# double_coil_driver.net
KiCad netlist of a schematic drawn in EAGLE
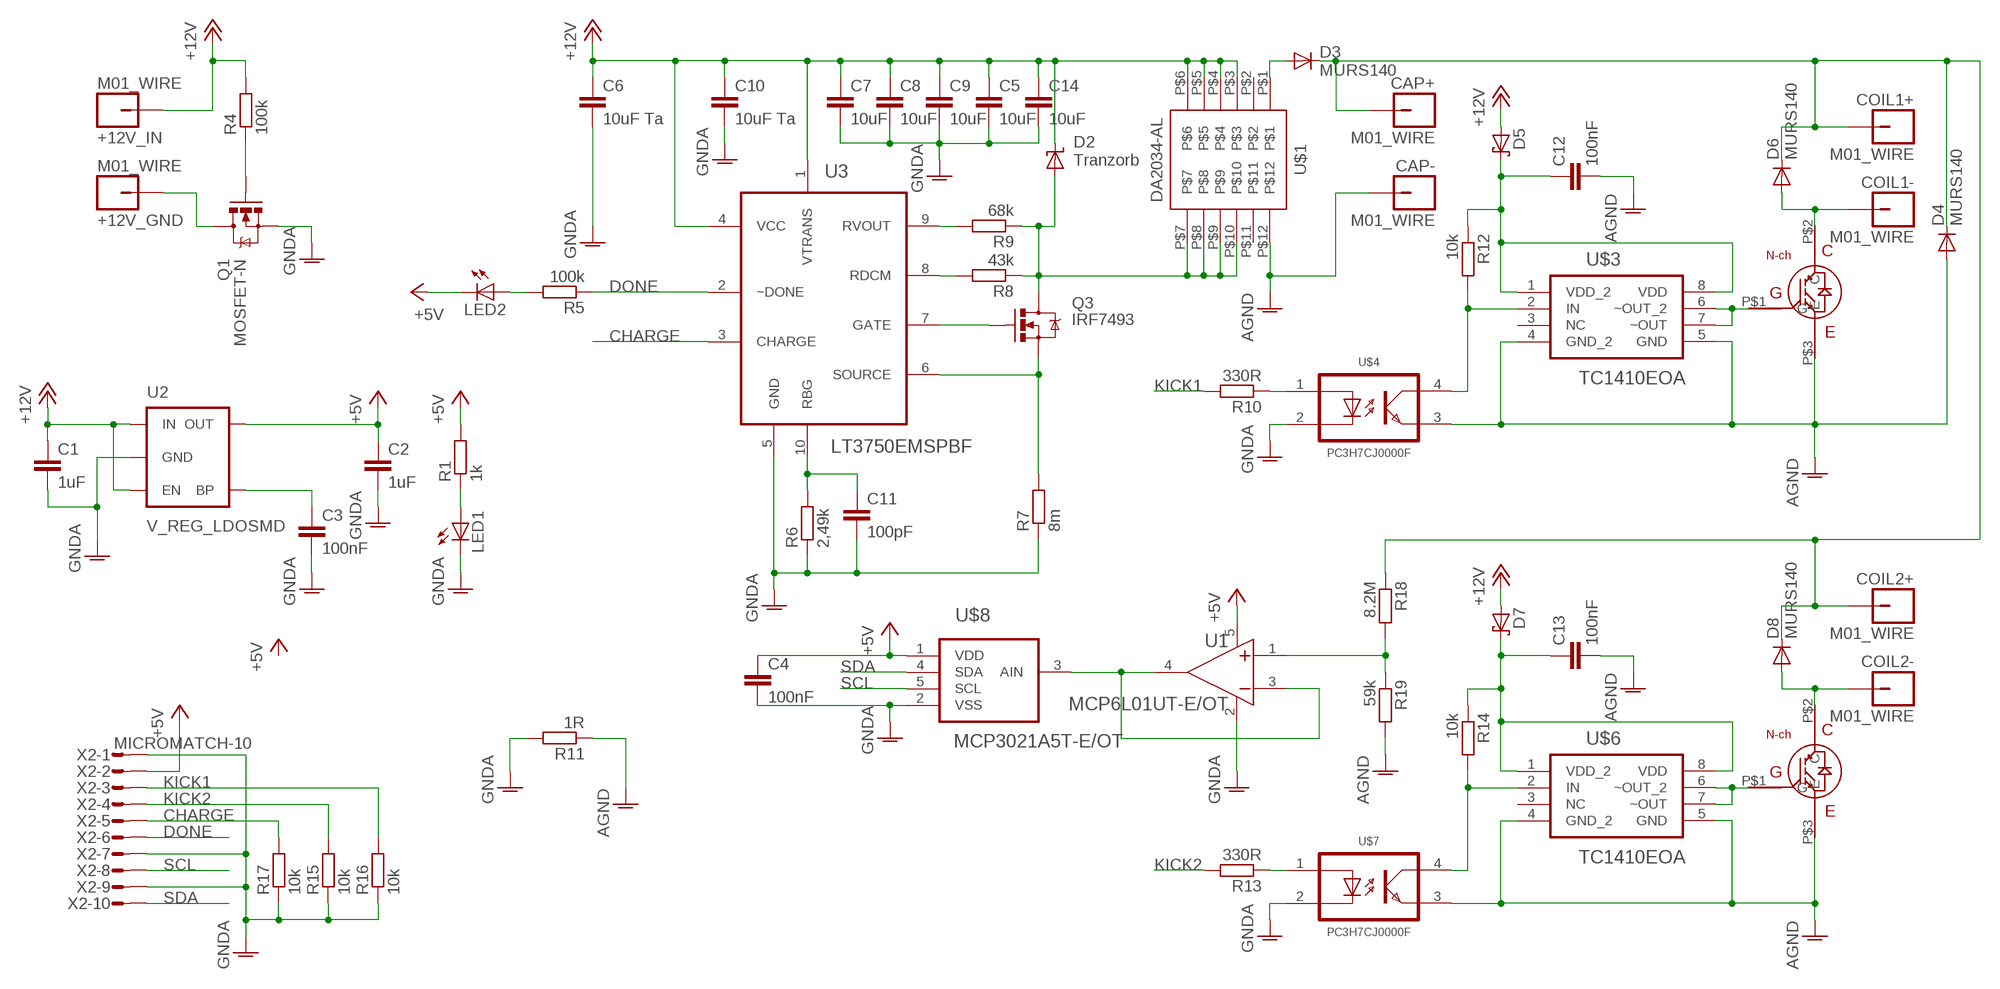
[diagram p0: schematic, sheet 1]

(export (version "E")
  (design (tool "Eeschema 10.0.6"))
  (components
    (comp (ref "+12V_GND")
      (value "M01_WIRE")
      (footprint "eagle-import:WIRE_HOLE")
      (libsource (lib "eagle-import") (part "M01_WIRE"))
    )
    (comp (ref "+12V_IN")
      (value "M01_WIRE")
      (footprint "eagle-import:WIRE_HOLE")
      (libsource (lib "eagle-import") (part "M01_WIRE"))
    )
    (comp (ref "C1")
      (value "1uF")
      (footprint "eagle-import:C1206K")
      (libsource (lib "eagle-import") (part "C-EUC1206K"))
    )
    (comp (ref "C2")
      (value "1uF")
      (footprint "eagle-import:C1206K")
      (libsource (lib "eagle-import") (part "C-EUC1206K"))
    )
    (comp (ref "C3")
      (value "100nF")
      (footprint "eagle-import:C0603K")
      (libsource (lib "eagle-import") (part "C-EUC0603K"))
    )
    (comp (ref "C4")
      (value "100nF")
      (footprint "eagle-import:C0603K")
      (libsource (lib "eagle-import") (part "C-EUC0603K"))
    )
    (comp (ref "C5")
      (value "10uF")
      (footprint "eagle-import:C1210K")
      (libsource (lib "eagle-import") (part "C-EUC1210K"))
    )
    (comp (ref "C6")
      (value "10uF Ta")
      (footprint "eagle-import:C1210K")
      (libsource (lib "eagle-import") (part "C-EUC1210K"))
    )
    (comp (ref "C7")
      (value "10uF")
      (footprint "eagle-import:C1210K")
      (libsource (lib "eagle-import") (part "C-EUC1210K"))
    )
    (comp (ref "C8")
      (value "10uF")
      (footprint "eagle-import:C1210K")
      (libsource (lib "eagle-import") (part "C-EUC1210K"))
    )
    (comp (ref "C9")
      (value "10uF")
      (footprint "eagle-import:C1210K")
      (libsource (lib "eagle-import") (part "C-EUC1210K"))
    )
    (comp (ref "C10")
      (value "10uF Ta")
      (footprint "eagle-import:C1210K")
      (libsource (lib "eagle-import") (part "C-EUC1210K"))
    )
    (comp (ref "C11")
      (value "100pF")
      (footprint "eagle-import:C0603")
      (libsource (lib "eagle-import") (part "C-EUC0603"))
    )
    (comp (ref "C12")
      (value "100nF")
      (footprint "eagle-import:C0603K")
      (libsource (lib "eagle-import") (part "C-EUC0603K"))
    )
    (comp (ref "C13")
      (value "100nF")
      (footprint "eagle-import:C0603K")
      (libsource (lib "eagle-import") (part "C-EUC0603K"))
    )
    (comp (ref "C14")
      (value "10uF")
      (footprint "eagle-import:C1210K")
      (libsource (lib "eagle-import") (part "C-EUC1210K"))
    )
    (comp (ref "CAP+")
      (value "M01_WIRE")
      (footprint "eagle-import:WIRE_HOLE")
      (libsource (lib "eagle-import") (part "M01_WIRE"))
    )
    (comp (ref "CAP-")
      (value "M01_WIRE")
      (footprint "eagle-import:WIRE_HOLE")
      (libsource (lib "eagle-import") (part "M01_WIRE"))
    )
    (comp (ref "COIL1+")
      (value "M01_WIRE")
      (footprint "eagle-import:WIRE_HOLE")
      (libsource (lib "eagle-import") (part "M01_WIRE"))
    )
    (comp (ref "COIL1-")
      (value "M01_WIRE")
      (footprint "eagle-import:WIRE_HOLE")
      (libsource (lib "eagle-import") (part "M01_WIRE"))
    )
    (comp (ref "COIL2+")
      (value "M01_WIRE")
      (footprint "eagle-import:WIRE_HOLE")
      (libsource (lib "eagle-import") (part "M01_WIRE"))
    )
    (comp (ref "COIL2-")
      (value "M01_WIRE")
      (footprint "eagle-import:WIRE_HOLE")
      (libsource (lib "eagle-import") (part "M01_WIRE"))
    )
    (comp (ref "D2")
      (value "Tranzorb")
      (footprint "eagle-import:SMC")
      (libsource (lib "eagle-import") (part "SUPPRESSOR-SMC"))
    )
    (comp (ref "D3")
      (value "MURS140")
      (footprint "eagle-import:DO214AA")
      (libsource (lib "eagle-import") (part "DIODE-DO214AA"))
    )
    (comp (ref "D4")
      (value "MURS140")
      (footprint "eagle-import:DO214AA")
      (libsource (lib "eagle-import") (part "DIODE-DO214AA"))
    )
    (comp (ref "D5")
      (value "SCHOTTKY-DIODE")
      (footprint "eagle-import:SOD123")
      (libsource (lib "eagle-import") (part "SCHOTTKY-DIODE"))
    )
    (comp (ref "D6")
      (value "MURS140")
      (footprint "eagle-import:DO214AA")
      (libsource (lib "eagle-import") (part "DIODE-DO214AA"))
    )
    (comp (ref "D7")
      (value "SCHOTTKY-DIODE")
      (footprint "eagle-import:SOD123")
      (libsource (lib "eagle-import") (part "SCHOTTKY-DIODE"))
    )
    (comp (ref "D8")
      (value "MURS140")
      (footprint "eagle-import:DO214AA")
      (libsource (lib "eagle-import") (part "DIODE-DO214AA"))
    )
    (comp (ref "LED1")
      (value "LEDCHIP-LED0603")
      (footprint "eagle-import:CHIP-LED0603")
      (libsource (lib "eagle-import") (part "LEDCHIP-LED0603"))
    )
    (comp (ref "LED2")
      (value "LEDCHIP-LED0603")
      (footprint "eagle-import:CHIP-LED0603")
      (libsource (lib "eagle-import") (part "LEDCHIP-LED0603"))
    )
    (comp (ref "Q1")
      (value "MOSFET-N")
      (footprint "eagle-import:SO08")
      (libsource (lib "eagle-import") (part "MOSFET-NCHANNELFDS6630A"))
    )
    (comp (ref "Q3")
      (value "IRF7493")
      (footprint "eagle-import:SO08")
      (libsource (lib "eagle-import") (part "MOSFET-NCHANNELFDS6630A"))
    )
    (comp (ref "R1")
      (value "1k")
      (footprint "eagle-import:R0603")
      (libsource (lib "eagle-import") (part "R-EU_R0603"))
    )
    (comp (ref "R4")
      (value "100k")
      (footprint "eagle-import:R0603")
      (libsource (lib "eagle-import") (part "R-EU_R0603"))
    )
    (comp (ref "R5")
      (value "100k")
      (footprint "eagle-import:R0603")
      (libsource (lib "eagle-import") (part "R-EU_R0603"))
    )
    (comp (ref "R6")
      (value "2,49k")
      (footprint "eagle-import:R0603")
      (libsource (lib "eagle-import") (part "R-EU_R0603"))
    )
    (comp (ref "R7")
      (value "8m")
      (footprint "eagle-import:R2010")
      (libsource (lib "eagle-import") (part "R-EU_R2010"))
    )
    (comp (ref "R8")
      (value "43k")
      (footprint "eagle-import:R0603")
      (libsource (lib "eagle-import") (part "R-EU_R0603"))
    )
    (comp (ref "R9")
      (value "68k")
      (footprint "eagle-import:R0603")
      (libsource (lib "eagle-import") (part "R-EU_R0603"))
    )
    (comp (ref "R10")
      (value "330R")
      (footprint "eagle-import:R0603")
      (libsource (lib "eagle-import") (part "R-EU_R0603"))
    )
    (comp (ref "R11")
      (value "1R")
      (footprint "eagle-import:R0603")
      (libsource (lib "eagle-import") (part "R-EU_R0603"))
    )
    (comp (ref "R12")
      (value "10k")
      (footprint "eagle-import:R0603")
      (libsource (lib "eagle-import") (part "R-EU_R0603"))
    )
    (comp (ref "R13")
      (value "330R")
      (footprint "eagle-import:R0603")
      (libsource (lib "eagle-import") (part "R-EU_R0603"))
    )
    (comp (ref "R14")
      (value "10k")
      (footprint "eagle-import:R0603")
      (libsource (lib "eagle-import") (part "R-EU_R0603"))
    )
    (comp (ref "R15")
      (value "10k")
      (footprint "eagle-import:R0603")
      (libsource (lib "eagle-import") (part "R-EU_R0603"))
    )
    (comp (ref "R16")
      (value "10k")
      (footprint "eagle-import:R0603")
      (libsource (lib "eagle-import") (part "R-EU_R0603"))
    )
    (comp (ref "R17")
      (value "10k")
      (footprint "eagle-import:R0603")
      (libsource (lib "eagle-import") (part "R-EU_R0603"))
    )
    (comp (ref "R18")
      (value "8.2M")
      (footprint "eagle-import:R0603")
      (libsource (lib "eagle-import") (part "R-EU_R0603"))
    )
    (comp (ref "R19")
      (value "59k")
      (footprint "eagle-import:R0603")
      (libsource (lib "eagle-import") (part "R-EU_R0603"))
    )
    (comp (ref "U$1")
      (value "DA2034-AL")
      (footprint "eagle-import:DA2034-AL")
      (libsource (lib "eagle-import") (part "DA2034-AL-SQUARE"))
    )
    (comp (ref "U$2")
      (value "TO-247A")
      (footprint "eagle-import:TO-247")
      (libsource (lib "eagle-import") (part "TO-247A"))
    )
    (comp (ref "U$3")
      (value "TC1410EOA")
      (footprint "eagle-import:SOIC127P600X175-8N")
      (libsource (lib "eagle-import") (part "TC1410EOA"))
    )
    (comp (ref "U$4")
      (value "PC3H7CJ0000F")
      (footprint "eagle-import:MINI-FLAT-HALF-PITCH-4")
      (libsource (lib "eagle-import") (part "PC3H7CJ0000F"))
    )
    (comp (ref "U$5")
      (value "TO-247A")
      (footprint "eagle-import:TO-247")
      (libsource (lib "eagle-import") (part "TO-247A"))
    )
    (comp (ref "U$6")
      (value "TC1410EOA")
      (footprint "eagle-import:SOIC127P600X175-8N")
      (libsource (lib "eagle-import") (part "TC1410EOA"))
    )
    (comp (ref "U$7")
      (value "PC3H7CJ0000F")
      (footprint "eagle-import:MINI-FLAT-HALF-PITCH-4")
      (libsource (lib "eagle-import") (part "PC3H7CJ0000F"))
    )
    (comp (ref "U$8")
      (value "MCP3021A5T-E/OT")
      (footprint "eagle-import:SOT95P270X145-5N")
      (libsource (lib "eagle-import") (part "MCP3021A5T-E/OT"))
    )
    (comp (ref "U1")
      (value "MCP6L01UT-E/OT")
      (footprint "eagle-import:SOT95P270X145-5N")
      (libsource (lib "eagle-import") (part "MCP6L01UT-E/OT"))
    )
    (comp (ref "U2")
      (value "V_REG_LDOSMD")
      (footprint "eagle-import:SOT23-5")
      (libsource (lib "eagle-import") (part "V_REG_LDOSMD"))
    )
    (comp (ref "U3")
      (value "LT3750EMSPBF")
      (footprint "eagle-import:SOP50P490X110-10N")
      (fields (field (name "MPN") "LT3750EMS#PBF"))
      (libsource (lib "eagle-import") (part "LT3750EMSPBF"))
    )
    (comp (ref "X2")
      (value "MICROMATCH-10")
      (footprint "eagle-import:MICROMATCH-10")
      (fields (field (name "MF") "FARNELL") (field (name "MPN") "8-215464-0"))
      (libsource (lib "eagle-import") (part "MICROMATCH-10"))
    )
  )
  (nets
    (net (code "1") (name "+5V") (class "Default")
      (node (ref "C2") (pin "1") (pinfunction "1_1") (pintype "passive"))
      (node (ref "C4") (pin "1") (pinfunction "1_1") (pintype "passive"))
      (node (ref "LED2") (pin "C") (pinfunction "C_C") (pintype "passive"))
      (node (ref "R1") (pin "2") (pinfunction "2_2") (pintype "passive"))
      (node (ref "U$8") (pin "1") (pinfunction "VDD_1") (pintype "power_in"))
      (node (ref "U1") (pin "5") (pinfunction "VDD_5") (pintype "power_in"))
      (node (ref "U2") (pin "5") (pinfunction "OUT_5") (pintype "passive"))
      (node (ref "X2") (pin "2") (pinfunction "S_2") (pintype "passive"))
    )
    (net (code "2") (name "+12V") (class "Default")
      (node (ref "+12V_IN") (pin "P$1") (pinfunction "P$1_P$1") (pintype "bidirectional"))
      (node (ref "C1") (pin "1") (pinfunction "1_1") (pintype "passive"))
      (node (ref "C10") (pin "1") (pinfunction "1_1") (pintype "passive"))
      (node (ref "C14") (pin "1") (pinfunction "1_1") (pintype "passive"))
      (node (ref "C5") (pin "1") (pinfunction "1_1") (pintype "passive"))
      (node (ref "C6") (pin "1") (pinfunction "1_1") (pintype "passive"))
      (node (ref "C7") (pin "1") (pinfunction "1_1") (pintype "passive"))
      (node (ref "C8") (pin "1") (pinfunction "1_1") (pintype "passive"))
      (node (ref "C9") (pin "1") (pinfunction "1_1") (pintype "passive"))
      (node (ref "D2") (pin "C") (pinfunction "C_C") (pintype "passive"))
      (node (ref "D5") (pin "A") (pinfunction "A_A") (pintype "passive"))
      (node (ref "D7") (pin "A") (pinfunction "A_A") (pintype "passive"))
      (node (ref "R4") (pin "2") (pinfunction "2_2") (pintype "passive"))
      (node (ref "U$1") (pin "P$3") (pinfunction "P$3_P$3") (pintype "bidirectional"))
      (node (ref "U$1") (pin "P$4") (pinfunction "P$4_P$4") (pintype "bidirectional"))
      (node (ref "U$1") (pin "P$5") (pinfunction "P$5_P$5") (pintype "bidirectional"))
      (node (ref "U$1") (pin "P$6") (pinfunction "P$6_P$6") (pintype "bidirectional"))
      (node (ref "U2") (pin "1") (pinfunction "IN_1") (pintype "input"))
      (node (ref "U2") (pin "3") (pinfunction "EN_3") (pintype "input"))
      (node (ref "U3") (pin "1") (pinfunction "VTRANS_1") (pintype "power_in"))
      (node (ref "U3") (pin "4") (pinfunction "VCC_4") (pintype "power_in"))
    )
    (net (code "3") (name "/CHARGE") (class "Default")
      (node (ref "R17") (pin "2") (pinfunction "2_2") (pintype "passive"))
      (node (ref "U3") (pin "3") (pinfunction "CHARGE_3") (pintype "input"))
      (node (ref "X2") (pin "5") (pinfunction "S_5") (pintype "passive"))
    )
    (net (code "4") (name "/DONE") (class "Default")
      (node (ref "R5") (pin "1") (pinfunction "1_1") (pintype "passive"))
      (node (ref "U3") (pin "2") (pinfunction "~{DONE}_2") (pintype "input"))
      (node (ref "X2") (pin "6") (pinfunction "S_6") (pintype "passive"))
    )
    (net (code "5") (name "/KICK1") (class "Default")
      (node (ref "R10") (pin "2") (pinfunction "2_2") (pintype "passive"))
      (node (ref "R16") (pin "2") (pinfunction "2_2") (pintype "passive"))
      (node (ref "X2") (pin "3") (pinfunction "S_3") (pintype "passive"))
    )
    (net (code "6") (name "/KICK2") (class "Default")
      (node (ref "R13") (pin "2") (pinfunction "2_2") (pintype "passive"))
      (node (ref "R15") (pin "2") (pinfunction "2_2") (pintype "passive"))
      (node (ref "X2") (pin "4") (pinfunction "S_4") (pintype "passive"))
    )
    (net (code "7") (name "/SCL") (class "Default")
      (node (ref "U$8") (pin "5") (pinfunction "SCL_5") (pintype "input"))
      (node (ref "X2") (pin "8") (pinfunction "S_8") (pintype "passive"))
    )
    (net (code "8") (name "/SDA") (class "Default")
      (node (ref "U$8") (pin "4") (pinfunction "SDA_4") (pintype "bidirectional"))
      (node (ref "X2") (pin "10") (pinfunction "S_10") (pintype "passive"))
    )
    (net (code "9") (name "AGND") (class "Default")
      (node (ref "C12") (pin "2") (pinfunction "2_2") (pintype "passive"))
      (node (ref "C13") (pin "2") (pinfunction "2_2") (pintype "passive"))
      (node (ref "CAP-") (pin "P$1") (pinfunction "P$1_P$1") (pintype "bidirectional"))
      (node (ref "D4") (pin "A") (pinfunction "A_A") (pintype "passive"))
      (node (ref "R11") (pin "1") (pinfunction "1_1") (pintype "passive"))
      (node (ref "R19") (pin "2") (pinfunction "2_2") (pintype "passive"))
      (node (ref "U$1") (pin "P$12") (pinfunction "P$12_P$12") (pintype "bidirectional"))
      (node (ref "U$2") (pin "P$3") (pinfunction "E_P$3") (pintype "bidirectional"))
      (node (ref "U$3") (pin "4") (pinfunction "GND_2_4") (pintype "passive"))
      (node (ref "U$3") (pin "5") (pinfunction "GND_5") (pintype "passive"))
      (node (ref "U$4") (pin "3") (pinfunction "P$3_3") (pintype "output"))
      (node (ref "U$5") (pin "P$3") (pinfunction "E_P$3") (pintype "bidirectional"))
      (node (ref "U$6") (pin "4") (pinfunction "GND_2_4") (pintype "passive"))
      (node (ref "U$6") (pin "5") (pinfunction "GND_5") (pintype "passive"))
      (node (ref "U$7") (pin "3") (pinfunction "P$3_3") (pintype "output"))
    )
    (net (code "10") (name "GNDA") (class "Default")
      (node (ref "C1") (pin "2") (pinfunction "2_2") (pintype "passive"))
      (node (ref "C10") (pin "2") (pinfunction "2_2") (pintype "passive"))
      (node (ref "C11") (pin "2") (pinfunction "2_2") (pintype "passive"))
      (node (ref "C14") (pin "2") (pinfunction "2_2") (pintype "passive"))
      (node (ref "C2") (pin "2") (pinfunction "2_2") (pintype "passive"))
      (node (ref "C3") (pin "2") (pinfunction "2_2") (pintype "passive"))
      (node (ref "C4") (pin "2") (pinfunction "2_2") (pintype "passive"))
      (node (ref "C5") (pin "2") (pinfunction "2_2") (pintype "passive"))
      (node (ref "C6") (pin "2") (pinfunction "2_2") (pintype "passive"))
      (node (ref "C7") (pin "2") (pinfunction "2_2") (pintype "passive"))
      (node (ref "C8") (pin "2") (pinfunction "2_2") (pintype "passive"))
      (node (ref "C9") (pin "2") (pinfunction "2_2") (pintype "passive"))
      (node (ref "LED1") (pin "C") (pinfunction "C_C") (pintype "passive"))
      (node (ref "Q1") (pin "1") (pinfunction "S_1") (pintype "passive"))
      (node (ref "Q1") (pin "2") (pinfunction "S_2") (pintype "passive"))
      (node (ref "Q1") (pin "3") (pinfunction "S_3") (pintype "passive"))
      (node (ref "R11") (pin "2") (pinfunction "2_2") (pintype "passive"))
      (node (ref "R15") (pin "1") (pinfunction "1_1") (pintype "passive"))
      (node (ref "R16") (pin "1") (pinfunction "1_1") (pintype "passive"))
      (node (ref "R17") (pin "1") (pinfunction "1_1") (pintype "passive"))
      (node (ref "R6") (pin "1") (pinfunction "1_1") (pintype "passive"))
      (node (ref "R7") (pin "1") (pinfunction "1_1") (pintype "passive"))
      (node (ref "U$4") (pin "2") (pinfunction "P$2_2") (pintype "output"))
      (node (ref "U$7") (pin "2") (pinfunction "P$2_2") (pintype "output"))
      (node (ref "U$8") (pin "2") (pinfunction "VSS_2") (pintype "passive"))
      (node (ref "U1") (pin "2") (pinfunction "VSS_2") (pintype "power_in"))
      (node (ref "U2") (pin "2") (pinfunction "GND_2") (pintype "input"))
      (node (ref "U3") (pin "5") (pinfunction "GND_5") (pintype "passive"))
      (node (ref "X2") (pin "1") (pinfunction "S_1") (pintype "passive"))
      (node (ref "X2") (pin "7") (pinfunction "S_7") (pintype "passive"))
      (node (ref "X2") (pin "9") (pinfunction "S_9") (pintype "passive"))
    )
    (net (code "11") (name "Net-(+12V_GND-PadP$1)") (class "Default")
      (node (ref "+12V_GND") (pin "P$1") (pinfunction "P$1_P$1") (pintype "bidirectional"))
      (node (ref "Q1") (pin "5") (pinfunction "D_5") (pintype "passive"))
      (node (ref "Q1") (pin "6") (pinfunction "D_6") (pintype "passive"))
      (node (ref "Q1") (pin "7") (pinfunction "D_7") (pintype "passive"))
      (node (ref "Q1") (pin "8") (pinfunction "D_8") (pintype "passive"))
    )
    (net (code "12") (name "Net-(CAP+-PadP$1)") (class "Default")
      (node (ref "CAP+") (pin "P$1") (pinfunction "P$1_P$1") (pintype "bidirectional"))
      (node (ref "COIL1+") (pin "P$1") (pinfunction "P$1_P$1") (pintype "bidirectional"))
      (node (ref "COIL2+") (pin "P$1") (pinfunction "P$1_P$1") (pintype "bidirectional"))
      (node (ref "D3") (pin "C") (pinfunction "C_C") (pintype "passive"))
      (node (ref "D4") (pin "C") (pinfunction "C_C") (pintype "passive"))
      (node (ref "D6") (pin "C") (pinfunction "C_C") (pintype "passive"))
      (node (ref "D8") (pin "C") (pinfunction "C_C") (pintype "passive"))
      (node (ref "R18") (pin "1") (pinfunction "1_1") (pintype "passive"))
    )
    (net (code "13") (name "Net-(D2-PadA)") (class "Default")
      (node (ref "D2") (pin "A") (pinfunction "A_A") (pintype "passive"))
      (node (ref "Q3") (pin "5") (pinfunction "D_5") (pintype "passive"))
      (node (ref "Q3") (pin "6") (pinfunction "D_6") (pintype "passive"))
      (node (ref "Q3") (pin "7") (pinfunction "D_7") (pintype "passive"))
      (node (ref "Q3") (pin "8") (pinfunction "D_8") (pintype "passive"))
      (node (ref "R8") (pin "1") (pinfunction "1_1") (pintype "passive"))
      (node (ref "R9") (pin "1") (pinfunction "1_1") (pintype "passive"))
      (node (ref "U$1") (pin "P$10") (pinfunction "P$10_P$10") (pintype "bidirectional"))
      (node (ref "U$1") (pin "P$7") (pinfunction "P$7_P$7") (pintype "bidirectional"))
      (node (ref "U$1") (pin "P$8") (pinfunction "P$8_P$8") (pintype "bidirectional"))
      (node (ref "U$1") (pin "P$9") (pinfunction "P$9_P$9") (pintype "bidirectional"))
    )
    (net (code "14") (name "Net-(D3-PadA)") (class "Default")
      (node (ref "D3") (pin "A") (pinfunction "A_A") (pintype "passive"))
      (node (ref "U$1") (pin "P$1") (pinfunction "P$1_P$1") (pintype "bidirectional"))
    )
    (net (code "15") (name "Net-(LED1-PadA)") (class "Default")
      (node (ref "LED1") (pin "A") (pinfunction "A_A") (pintype "passive"))
      (node (ref "R1") (pin "1") (pinfunction "1_1") (pintype "passive"))
    )
    (net (code "16") (name "Net-(LED2-PadA)") (class "Default")
      (node (ref "LED2") (pin "A") (pinfunction "A_A") (pintype "passive"))
      (node (ref "R5") (pin "2") (pinfunction "2_2") (pintype "passive"))
    )
    (net (code "17") (name "Net-(Q1-G)") (class "Default")
      (node (ref "Q1") (pin "4") (pinfunction "G_4") (pintype "passive"))
      (node (ref "R4") (pin "1") (pinfunction "1_1") (pintype "passive"))
    )
    (net (code "18") (name "Net-(Q3-G)") (class "Default")
      (node (ref "Q3") (pin "4") (pinfunction "G_4") (pintype "passive"))
      (node (ref "U3") (pin "7") (pinfunction "GATE_7") (pintype "input"))
    )
    (net (code "19") (name "Net-(U$2-C)") (class "Default")
      (node (ref "COIL1-") (pin "P$1") (pinfunction "P$1_P$1") (pintype "bidirectional"))
      (node (ref "D6") (pin "A") (pinfunction "A_A") (pintype "passive"))
      (node (ref "U$2") (pin "P$2") (pinfunction "C_P$2") (pintype "bidirectional"))
    )
    (net (code "20") (name "Net-(U$2-G)") (class "Default")
      (node (ref "U$2") (pin "P$1") (pinfunction "G_P$1") (pintype "bidirectional"))
      (node (ref "U$3") (pin "6") (pinfunction "~{OUT_2}_6") (pintype "output"))
      (node (ref "U$3") (pin "7") (pinfunction "~{OUT}_7") (pintype "output"))
    )
    (net (code "21") (name "Net-(U$3-IN)") (class "Default")
      (node (ref "R12") (pin "2") (pinfunction "2_2") (pintype "passive"))
      (node (ref "U$3") (pin "2") (pinfunction "IN_2") (pintype "input"))
      (node (ref "U$4") (pin "4") (pinfunction "P$4_4") (pintype "output"))
    )
    (net (code "22") (name "Net-(U$3-VDD)") (class "Default")
      (node (ref "C12") (pin "1") (pinfunction "1_1") (pintype "passive"))
      (node (ref "D5") (pin "C") (pinfunction "C_C") (pintype "passive"))
      (node (ref "R12") (pin "1") (pinfunction "1_1") (pintype "passive"))
      (node (ref "U$3") (pin "1") (pinfunction "VDD_2_1") (pintype "power_in"))
      (node (ref "U$3") (pin "8") (pinfunction "VDD_8") (pintype "power_in"))
    )
    (net (code "23") (name "Net-(U$4-P$1)") (class "Default")
      (node (ref "R10") (pin "1") (pinfunction "1_1") (pintype "passive"))
      (node (ref "U$4") (pin "1") (pinfunction "P$1_1") (pintype "output"))
    )
    (net (code "24") (name "Net-(U$5-C)") (class "Default")
      (node (ref "COIL2-") (pin "P$1") (pinfunction "P$1_P$1") (pintype "bidirectional"))
      (node (ref "D8") (pin "A") (pinfunction "A_A") (pintype "passive"))
      (node (ref "U$5") (pin "P$2") (pinfunction "C_P$2") (pintype "bidirectional"))
    )
    (net (code "25") (name "Net-(U$5-G)") (class "Default")
      (node (ref "U$5") (pin "P$1") (pinfunction "G_P$1") (pintype "bidirectional"))
      (node (ref "U$6") (pin "6") (pinfunction "~{OUT_2}_6") (pintype "output"))
      (node (ref "U$6") (pin "7") (pinfunction "~{OUT}_7") (pintype "output"))
    )
    (net (code "26") (name "Net-(U$6-IN)") (class "Default")
      (node (ref "R14") (pin "2") (pinfunction "2_2") (pintype "passive"))
      (node (ref "U$6") (pin "2") (pinfunction "IN_2") (pintype "input"))
      (node (ref "U$7") (pin "4") (pinfunction "P$4_4") (pintype "output"))
    )
    (net (code "27") (name "Net-(U$6-VDD)") (class "Default")
      (node (ref "C13") (pin "1") (pinfunction "1_1") (pintype "passive"))
      (node (ref "D7") (pin "C") (pinfunction "C_C") (pintype "passive"))
      (node (ref "R14") (pin "1") (pinfunction "1_1") (pintype "passive"))
      (node (ref "U$6") (pin "1") (pinfunction "VDD_2_1") (pintype "power_in"))
      (node (ref "U$6") (pin "8") (pinfunction "VDD_8") (pintype "power_in"))
    )
    (net (code "28") (name "Net-(U$7-P$1)") (class "Default")
      (node (ref "R13") (pin "1") (pinfunction "1_1") (pintype "passive"))
      (node (ref "U$7") (pin "1") (pinfunction "P$1_1") (pintype "output"))
    )
    (net (code "29") (name "Net-(U$8-AIN)") (class "Default")
      (node (ref "U$8") (pin "3") (pinfunction "AIN_3") (pintype "input"))
      (node (ref "U1") (pin "3") (pinfunction "VIN-_3") (pintype "input"))
      (node (ref "U1") (pin "4") (pinfunction "VOUT_4") (pintype "output"))
    )
    (net (code "30") (name "Net-(U1-VIN+)") (class "Default")
      (node (ref "R18") (pin "2") (pinfunction "2_2") (pintype "passive"))
      (node (ref "R19") (pin "1") (pinfunction "1_1") (pintype "passive"))
      (node (ref "U1") (pin "1") (pinfunction "VIN+_1") (pintype "input"))
    )
    (net (code "31") (name "Net-(U2-BP)") (class "Default")
      (node (ref "C3") (pin "1") (pinfunction "1_1") (pintype "passive"))
      (node (ref "U2") (pin "4") (pinfunction "BP_4") (pintype "input"))
    )
    (net (code "32") (name "Net-(U3-RBG)") (class "Default")
      (node (ref "C11") (pin "1") (pinfunction "1_1") (pintype "passive"))
      (node (ref "R6") (pin "2") (pinfunction "2_2") (pintype "passive"))
      (node (ref "U3") (pin "10") (pinfunction "RBG_10") (pintype "input"))
    )
    (net (code "33") (name "Net-(U3-RDCM)") (class "Default")
      (node (ref "R8") (pin "2") (pinfunction "2_2") (pintype "passive"))
      (node (ref "U3") (pin "8") (pinfunction "RDCM_8") (pintype "input"))
    )
    (net (code "34") (name "Net-(U3-RVOUT)") (class "Default")
      (node (ref "R9") (pin "2") (pinfunction "2_2") (pintype "passive"))
      (node (ref "U3") (pin "9") (pinfunction "RVOUT_9") (pintype "output"))
    )
    (net (code "35") (name "Net-(U3-SOURCE)") (class "Default")
      (node (ref "Q3") (pin "1") (pinfunction "S_1") (pintype "passive"))
      (node (ref "Q3") (pin "2") (pinfunction "S_2") (pintype "passive"))
      (node (ref "Q3") (pin "3") (pinfunction "S_3") (pintype "passive"))
      (node (ref "R7") (pin "2") (pinfunction "2_2") (pintype "passive"))
      (node (ref "U3") (pin "6") (pinfunction "SOURCE_6") (pintype "input"))
    )
    (net (code "36") (name "unconnected-(U$1-PadP$2)") (class "Default")
      (node (ref "U$1") (pin "P$2") (pinfunction "P$2_P$2") (pintype "bidirectional"))
    )
    (net (code "37") (name "unconnected-(U$1-PadP$11)") (class "Default")
      (node (ref "U$1") (pin "P$11") (pinfunction "P$11_P$11") (pintype "bidirectional"))
    )
    (net (code "38") (name "unconnected-(U$3-NC-Pad3)") (class "Default")
      (node (ref "U$3") (pin "3") (pinfunction "NC_3") (pintype "no_connect"))
    )
    (net (code "39") (name "unconnected-(U$6-NC-Pad3)") (class "Default")
      (node (ref "U$6") (pin "3") (pinfunction "NC_3") (pintype "no_connect"))
    )
  )
)
